# alim.net
KiCad netlist of a schematic drawn in EAGLE
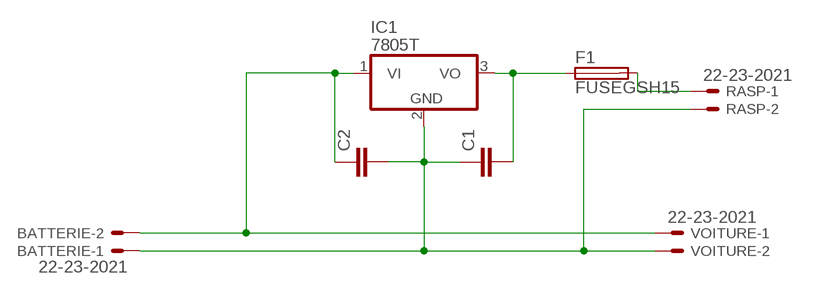
[diagram p0: schematic, sheet 1]

(export (version "E")
  (design (tool "Eeschema 10.0.6"))
  (components
    (comp (ref "BATTERIE")
      (value "22-23-2021")
      (footprint "eagle-import:22-23-2021")
      (fields (field (name "MF") "MOLEX"))
      (libsource (lib "eagle-import") (part "22-23-2021"))
    )
    (comp (ref "C1")
      (value "C-EU025-025X050")
      (footprint "eagle-import:C025-025X050")
      (libsource (lib "eagle-import") (part "C-EU025-025X050"))
    )
    (comp (ref "C2")
      (value "C-EU025-025X050")
      (footprint "eagle-import:C025-025X050")
      (libsource (lib "eagle-import") (part "C-EU025-025X050"))
    )
    (comp (ref "F1")
      (value "FUSEGSH15")
      (footprint "eagle-import:GSH15")
      (libsource (lib "eagle-import") (part "FUSEGSH15"))
    )
    (comp (ref "IC1")
      (value "7805T")
      (footprint "eagle-import:TO220H")
      (libsource (lib "eagle-import") (part "78T05"))
    )
    (comp (ref "RASP")
      (value "22-23-2021")
      (footprint "eagle-import:22-23-2021")
      (fields (field (name "MF") "MOLEX"))
      (libsource (lib "eagle-import") (part "22-23-2021"))
    )
    (comp (ref "VOITURE")
      (value "22-23-2021")
      (footprint "eagle-import:22-23-2021")
      (fields (field (name "MF") "MOLEX"))
      (libsource (lib "eagle-import") (part "22-23-2021"))
    )
  )
  (nets
    (net (code "1") (name "Net-(BATTERIEA-S)") (class "Default")
      (node (ref "BATTERIE") (pin "1") (pinfunction "S_1") (pintype "passive"))
      (node (ref "C1") (pin "1") (pinfunction "1_1") (pintype "passive"))
      (node (ref "C2") (pin "2") (pinfunction "2_2") (pintype "passive"))
      (node (ref "IC1") (pin "2") (pinfunction "GND_2") (pintype "passive"))
      (node (ref "RASP") (pin "2") (pinfunction "S_2") (pintype "passive"))
      (node (ref "VOITURE") (pin "2") (pinfunction "S_2") (pintype "passive"))
    )
    (net (code "2") (name "Net-(BATTERIEB-S)") (class "Default")
      (node (ref "BATTERIE") (pin "2") (pinfunction "S_2") (pintype "passive"))
      (node (ref "C2") (pin "1") (pinfunction "1_1") (pintype "passive"))
      (node (ref "IC1") (pin "1") (pinfunction "VI_1") (pintype "input"))
      (node (ref "VOITURE") (pin "1") (pinfunction "S_1") (pintype "passive"))
    )
    (net (code "3") (name "Net-(IC1-VO)") (class "Default")
      (node (ref "C1") (pin "2") (pinfunction "2_2") (pintype "passive"))
      (node (ref "F1") (pin "1") (pinfunction "1_1") (pintype "passive"))
      (node (ref "IC1") (pin "3") (pinfunction "VO_3") (pintype "passive"))
    )
    (net (code "4") (name "Net-(RASPA-S)") (class "Default")
      (node (ref "F1") (pin "2") (pinfunction "2_2") (pintype "passive"))
      (node (ref "RASP") (pin "1") (pinfunction "S_1") (pintype "passive"))
    )
  )
)
